# STM32WL_LHCbit.net
KiCad netlist of a schematic drawn in Altium Designer
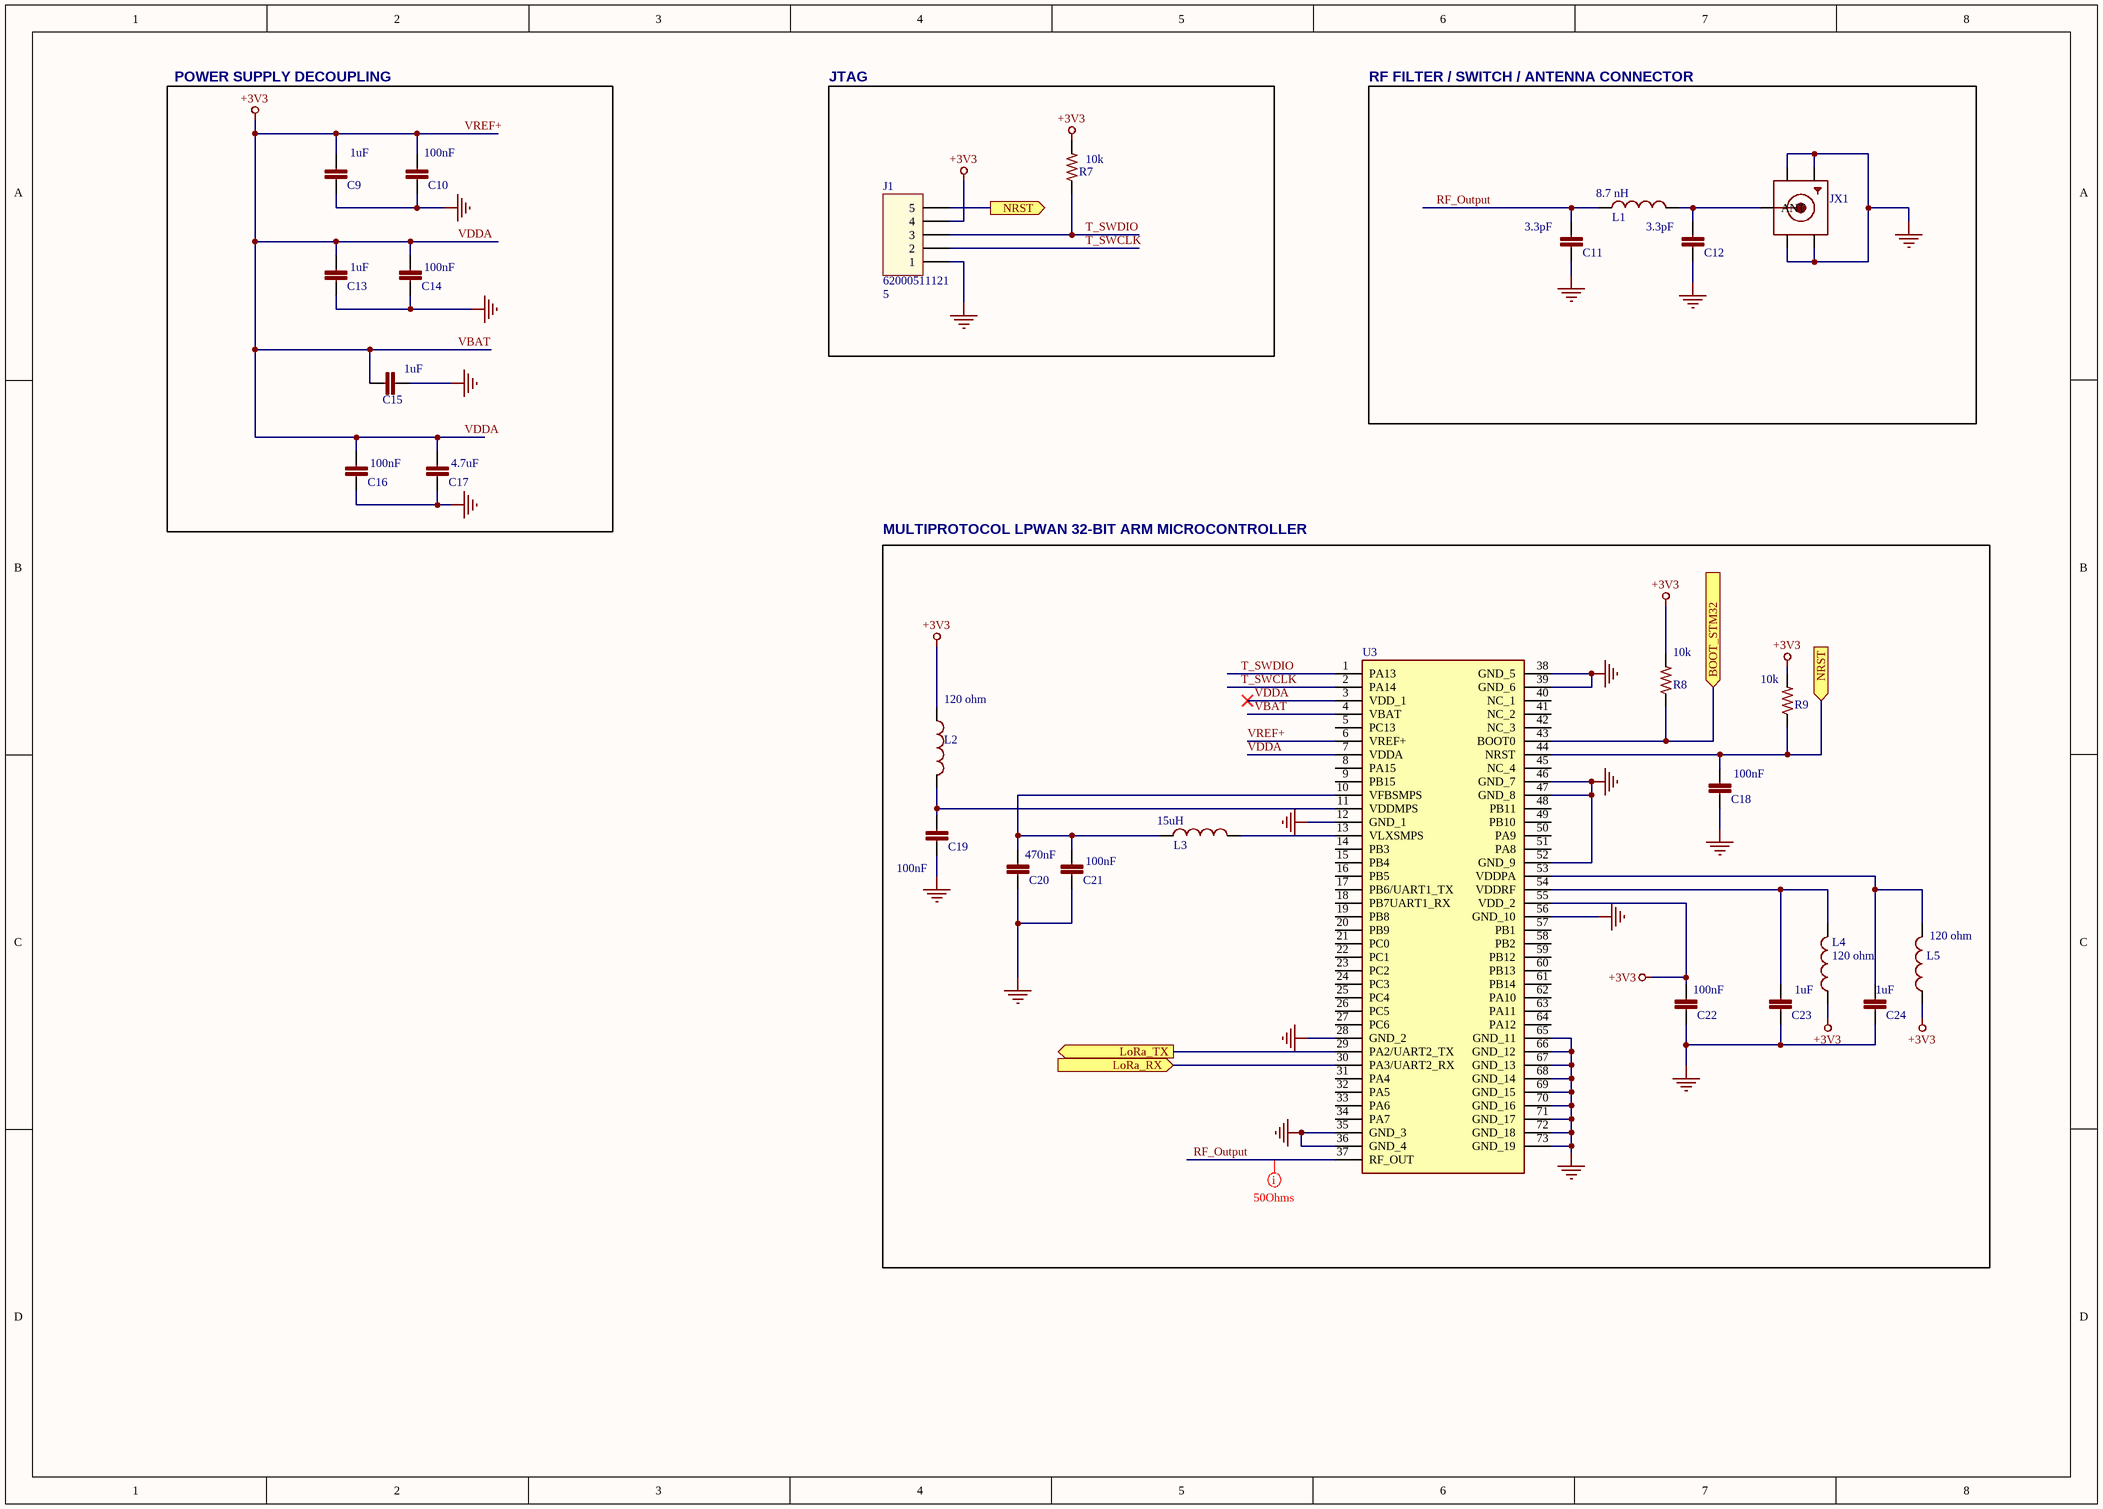
[diagram p0: STM32WL_LHCbit.SchDoc]

(export (version "E")
  (design (tool "Eeschema 10.0.6"))
  (components
    (comp (ref "C9")
      (value "1uF")
      (footprint "C0402")
      (fields (field (name "PART NUMBER") "GRM155C71C105KE11J") (field (name "Comment") "C-EUC0402"))
      (libsource (lib "") (part "C-EUC0402_1"))
    )
    (comp (ref "C10")
      (value "100nF")
      (footprint "C0402")
      (fields (field (name "PART NUMBER") "CGA2B3X7R1E104K050BB") (field (name "Comment") "C-EUC0402"))
      (libsource (lib "") (part "C-EUC0402_1"))
    )
    (comp (ref "C11")
      (value "3.3pF")
      (footprint "C0402")
      (fields (field (name "PART NUMBER") "GRM1555C1H3R3WA01D") (field (name "Comment") "C-EUC0402"))
      (libsource (lib "rcl") (part "C-EUC0402"))
    )
    (comp (ref "C12")
      (value "3.3pF")
      (footprint "C0402")
      (fields (field (name "PART NUMBER") "GRM1555C1H3R3WA01D") (field (name "Comment") "C-EUC0402"))
      (libsource (lib "rcl") (part "C-EUC0402"))
    )
    (comp (ref "C13")
      (value "1uF")
      (footprint "C0402")
      (fields (field (name "PART NUMBER") "GRM155C71C105KE11J") (field (name "Comment") "C-EUC0402"))
      (libsource (lib "") (part "C-EUC0402_1"))
    )
    (comp (ref "C14")
      (value "100nF")
      (footprint "C0402")
      (fields (field (name "PART NUMBER") "CGA2B3X7R1E104K050BB") (field (name "Comment") "C-EUC0402"))
      (libsource (lib "") (part "C-EUC0402_1"))
    )
    (comp (ref "C15")
      (value "1uF")
      (footprint "C0402")
      (fields (field (name "PART NUMBER") "GRM155C71C105KE11J") (field (name "Comment") "C-EUC0402"))
      (libsource (lib "") (part "C-EUC0402_2"))
    )
    (comp (ref "C16")
      (value "100nF")
      (footprint "C0402")
      (fields (field (name "PART NUMBER") "CGA2B3X7R1E104K050BB") (field (name "Comment") "C-EUC0402"))
      (libsource (lib "") (part "C-EUC0402_1"))
    )
    (comp (ref "C17")
      (value "4.7uF")
      (footprint "C0402")
      (fields (field (name "PART NUMBER") "GRM155D80E475ME47J") (field (name "Comment") "C-EUC0402"))
      (libsource (lib "") (part "C-EUC0402_1"))
    )
    (comp (ref "C18")
      (value "100nF")
      (footprint "C0402")
      (fields (field (name "PART NUMBER") "CGA2B3X7R1E104K050BB") (field (name "Comment") "C-EUC0402"))
      (libsource (lib "") (part "C-EUC0402_1"))
    )
    (comp (ref "C19")
      (value "100nF")
      (footprint "C0402")
      (fields (field (name "PART NUMBER") "CGA2B3X7R1E104K050BB") (field (name "Comment") "C-EUC0402"))
      (libsource (lib "") (part "C-EUC0402_1"))
    )
    (comp (ref "C20")
      (value "470nF")
      (footprint "C0402")
      (fields (field (name "PART NUMBER") "0603YD474KAT2A") (field (name "Comment") "C-EUC0402"))
      (libsource (lib "") (part "C-EUC0402_1"))
    )
    (comp (ref "C21")
      (value "100nF")
      (footprint "C0402")
      (fields (field (name "PART NUMBER") "CGA2B3X7R1E104K050BB") (field (name "Comment") "C-EUC0402"))
      (libsource (lib "") (part "C-EUC0402_1"))
    )
    (comp (ref "C22")
      (value "100nF")
      (footprint "C0402")
      (fields (field (name "PART NUMBER") "CGA2B3X7R1E104K050BB") (field (name "Comment") "C-EUC0402"))
      (libsource (lib "") (part "C-EUC0402_1"))
    )
    (comp (ref "C23")
      (value "1uF")
      (footprint "C0402")
      (fields (field (name "PART NUMBER") "GRM155C71C105KE11J") (field (name "Comment") "C-EUC0402"))
      (libsource (lib "") (part "C-EUC0402_1"))
    )
    (comp (ref "C24")
      (value "1uF")
      (footprint "C0402")
      (fields (field (name "PART NUMBER") "GRM155C71C105KE11J") (field (name "Comment") "C-EUC0402"))
      (libsource (lib "") (part "C-EUC0402_1"))
    )
    (comp (ref "J1")
      (value "62000511121")
      (footprint "62000511121")
      (description "WR-PHD 2.00 mm THT Pin Header, 6p")
      (fields (field (name "ALTIUM_VALUE") "5"))
      (libsource (lib "Male_header_200mm") (part "62000511121"))
    )
    (comp (ref "JX1")
      (value "SMACONNECTOR_EDGE_UFL")
      (footprint "SMA_EDGELAUNCH_UFL")
      (fields (field (name "PART NUMBER") "SMA-J-P-H-ST-EM1"))
      (libsource (lib "TE") (part "SMACONNECTOR_EDGE_UFL"))
    )
    (comp (ref "L1")
      (value "8.7 nH")
      (footprint "L0402 - rounded")
      (fields (field (name "PART NUMBER") "LQW15AN8N7G00D") (field (name "Comment") "Ferrite bead 0402"))
      (libsource (lib "rcl") (part "L-US0402"))
    )
    (comp (ref "L2")
      (value "120 ohm")
      (footprint "L0603")
      (fields (field (name "PART NUMBER") "ILHB0603ER121V") (field (name "Comment") "Ferrite bead 0603"))
      (libsource (lib "rcl") (part "L-US0603"))
    )
    (comp (ref "L3")
      (value "15uH")
      (footprint "L0805")
      (fields (field (name "PART NUMBER") "MLZ2012M150WTD25"))
      (libsource (lib "rcl") (part "L-US0805"))
    )
    (comp (ref "L4")
      (value "120 ohm")
      (footprint "L0603")
      (fields (field (name "PART NUMBER") "ILHB0603ER121V") (field (name "Comment") "Ferrite bead 0603"))
      (libsource (lib "rcl") (part "L-US0603"))
    )
    (comp (ref "L5")
      (value "120 ohm")
      (footprint "L0603")
      (fields (field (name "PART NUMBER") "ILHB0603ER121V") (field (name "Comment") "Ferrite bead 0603"))
      (libsource (lib "rcl") (part "L-US0603"))
    )
    (comp (ref "R7")
      (value "10k")
      (footprint "R0402")
      (fields (field (name "PART NUMBER") "CRCW040210K0FKEDC") (field (name "Comment") "R-US_R0402"))
      (libsource (lib "rcl") (part "R-US_R0402"))
    )
    (comp (ref "R8")
      (value "10k")
      (footprint "R0402")
      (fields (field (name "PART NUMBER") "CRCW040210K0FKEDC") (field (name "Comment") "R-US_R0402"))
      (libsource (lib "rcl") (part "R-US_R0402"))
    )
    (comp (ref "R9")
      (value "10k")
      (footprint "R0402")
      (fields (field (name "PART NUMBER") "CRCW040210K0FKEDC") (field (name "Comment") "R-US_R0402"))
      (libsource (lib "rcl") (part "R-US_R0402"))
    )
    (comp (ref "U3")
      (value "RAK3172-SiP")
      (footprint "RAK3172SiP")
      (description "Integrated Circuit")
      (libsource (lib "TE") (part "RAK3172-SiP"))
    )
  )
  (nets
    (net (code "1") (name "+3V3") (class "Default")
      (node (ref "C10") (pin "1") (pinfunction "1_1") (pintype "passive"))
      (node (ref "C13") (pin "1") (pinfunction "1_1") (pintype "passive"))
      (node (ref "C14") (pin "1") (pinfunction "1_1") (pintype "passive"))
      (node (ref "C15") (pin "1") (pinfunction "1_1") (pintype "passive"))
      (node (ref "C16") (pin "1") (pinfunction "1_1") (pintype "passive"))
      (node (ref "C17") (pin "1") (pinfunction "1_1") (pintype "passive"))
      (node (ref "C22") (pin "1") (pinfunction "1_1") (pintype "passive"))
      (node (ref "C9") (pin "1") (pinfunction "1_1") (pintype "passive"))
      (node (ref "J1") (pin "4") (pinfunction "4_4") (pintype "passive"))
      (node (ref "L2") (pin "1") (pinfunction "1_1") (pintype "passive"))
      (node (ref "L4") (pin "1") (pinfunction "1_1") (pintype "passive"))
      (node (ref "L5") (pin "1") (pinfunction "1_1") (pintype "passive"))
      (node (ref "R7") (pin "2") (pinfunction "2_2") (pintype "passive"))
      (node (ref "R8") (pin "2") (pinfunction "2_2") (pintype "passive"))
      (node (ref "R9") (pin "2") (pinfunction "2_2") (pintype "passive"))
      (node (ref "U3") (pin "3") (pinfunction "VDD_1_3") (pintype "passive"))
      (node (ref "U3") (pin "4") (pinfunction "VBAT_4") (pintype "passive"))
      (node (ref "U3") (pin "55") (pinfunction "VDD_2_55") (pintype "passive"))
      (node (ref "U3") (pin "6") (pinfunction "VREF+_6") (pintype "passive"))
      (node (ref "U3") (pin "7") (pinfunction "VDDA_7") (pintype "passive"))
    )
    (net (code "2") (name "/BOOT_STM32") (class "Default")
      (node (ref "R8") (pin "1") (pinfunction "1_1") (pintype "passive"))
      (node (ref "U3") (pin "43") (pinfunction "BOOT0_43") (pintype "passive"))
    )
    (net (code "3") (name "/LoRa_RX") (class "Default")
      (node (ref "U3") (pin "30") (pinfunction "PA3/UART2_RX_30") (pintype "passive"))
    )
    (net (code "4") (name "/LoRa_TX") (class "Default")
      (node (ref "U3") (pin "29") (pinfunction "PA2/UART2_TX_29") (pintype "passive"))
    )
    (net (code "5") (name "/NRST") (class "Default")
      (node (ref "C18") (pin "1") (pinfunction "1_1") (pintype "passive"))
      (node (ref "J1") (pin "5") (pinfunction "5_5") (pintype "passive"))
      (node (ref "R9") (pin "1") (pinfunction "1_1") (pintype "passive"))
      (node (ref "U3") (pin "44") (pinfunction "NRST_44") (pintype "passive"))
    )
    (net (code "6") (name "/RF_Output") (class "Default")
      (node (ref "C11") (pin "2") (pinfunction "2_2") (pintype "passive"))
      (node (ref "L1") (pin "1") (pinfunction "1_1") (pintype "passive"))
      (node (ref "U3") (pin "37") (pinfunction "RF_OUT_37") (pintype "passive"))
    )
    (net (code "7") (name "/T_SWCLK") (class "Default")
      (node (ref "J1") (pin "2") (pinfunction "2_2") (pintype "passive"))
      (node (ref "U3") (pin "2") (pinfunction "PA14_2") (pintype "passive"))
    )
    (net (code "8") (name "/T_SWDIO") (class "Default")
      (node (ref "J1") (pin "3") (pinfunction "3_3") (pintype "passive"))
      (node (ref "R7") (pin "1") (pinfunction "1_1") (pintype "passive"))
      (node (ref "U3") (pin "1") (pinfunction "PA13_1") (pintype "passive"))
    )
    (net (code "9") (name "GND") (class "Default")
      (node (ref "C10") (pin "2") (pinfunction "2_2") (pintype "passive"))
      (node (ref "C11") (pin "1") (pinfunction "1_1") (pintype "passive"))
      (node (ref "C12") (pin "1") (pinfunction "1_1") (pintype "passive"))
      (node (ref "C13") (pin "2") (pinfunction "2_2") (pintype "passive"))
      (node (ref "C14") (pin "2") (pinfunction "2_2") (pintype "passive"))
      (node (ref "C15") (pin "2") (pinfunction "2_2") (pintype "passive"))
      (node (ref "C16") (pin "2") (pinfunction "2_2") (pintype "passive"))
      (node (ref "C17") (pin "2") (pinfunction "2_2") (pintype "passive"))
      (node (ref "C18") (pin "2") (pinfunction "2_2") (pintype "passive"))
      (node (ref "C19") (pin "2") (pinfunction "2_2") (pintype "passive"))
      (node (ref "C20") (pin "2") (pinfunction "2_2") (pintype "passive"))
      (node (ref "C21") (pin "2") (pinfunction "2_2") (pintype "passive"))
      (node (ref "C22") (pin "2") (pinfunction "2_2") (pintype "passive"))
      (node (ref "C23") (pin "2") (pinfunction "2_2") (pintype "passive"))
      (node (ref "C24") (pin "2") (pinfunction "2_2") (pintype "passive"))
      (node (ref "C9") (pin "2") (pinfunction "2_2") (pintype "passive"))
      (node (ref "J1") (pin "1") (pinfunction "1_1") (pintype "passive"))
      (node (ref "JX1") (pin "GND@1") (pinfunction "GND1_GND@1") (pintype "power_in"))
      (node (ref "JX1") (pin "GND@2") (pinfunction "GND2_GND@2") (pintype "power_in"))
      (node (ref "JX1") (pin "GND@3") (pinfunction "GND3_GND@3") (pintype "power_in"))
      (node (ref "JX1") (pin "GND@4") (pinfunction "GND4_GND@4") (pintype "power_in"))
      (node (ref "U3") (pin "12") (pinfunction "GND_1_12") (pintype "passive"))
      (node (ref "U3") (pin "28") (pinfunction "GND_2_28") (pintype "passive"))
      (node (ref "U3") (pin "35") (pinfunction "GND_3_35") (pintype "passive"))
      (node (ref "U3") (pin "36") (pinfunction "GND_4_36") (pintype "passive"))
      (node (ref "U3") (pin "38") (pinfunction "GND_5_38") (pintype "passive"))
      (node (ref "U3") (pin "39") (pinfunction "GND_6_39") (pintype "passive"))
      (node (ref "U3") (pin "46") (pinfunction "GND_7_46") (pintype "passive"))
      (node (ref "U3") (pin "47") (pinfunction "GND_8_47") (pintype "passive"))
      (node (ref "U3") (pin "52") (pinfunction "GND_9_52") (pintype "passive"))
      (node (ref "U3") (pin "56") (pinfunction "GND_10_56") (pintype "passive"))
      (node (ref "U3") (pin "65") (pinfunction "GND_11_65") (pintype "passive"))
      (node (ref "U3") (pin "66") (pinfunction "GND_12_66") (pintype "passive"))
      (node (ref "U3") (pin "67") (pinfunction "GND_13_67") (pintype "passive"))
      (node (ref "U3") (pin "68") (pinfunction "GND_14_68") (pintype "passive"))
      (node (ref "U3") (pin "69") (pinfunction "GND_15_69") (pintype "passive"))
      (node (ref "U3") (pin "70") (pinfunction "GND_16_70") (pintype "passive"))
      (node (ref "U3") (pin "71") (pinfunction "GND_17_71") (pintype "passive"))
      (node (ref "U3") (pin "72") (pinfunction "GND_18_72") (pintype "passive"))
      (node (ref "U3") (pin "73") (pinfunction "GND_19_73") (pintype "passive"))
    )
    (net (code "10") (name "Net-(JX1-ANT)") (class "Default")
      (node (ref "C12") (pin "2") (pinfunction "2_2") (pintype "passive"))
      (node (ref "JX1") (pin "P") (pinfunction "ANT_P") (pintype "passive"))
      (node (ref "L1") (pin "2") (pinfunction "2_2") (pintype "passive"))
    )
    (net (code "11") (name "Net-(U3-VDDMPS)") (class "Default")
      (node (ref "C19") (pin "1") (pinfunction "1_1") (pintype "passive"))
      (node (ref "L2") (pin "2") (pinfunction "2_2") (pintype "passive"))
      (node (ref "U3") (pin "11") (pinfunction "VDDMPS_11") (pintype "passive"))
    )
    (net (code "12") (name "Net-(U3-VDDPA)") (class "Default")
      (node (ref "C24") (pin "1") (pinfunction "1_1") (pintype "passive"))
      (node (ref "L5") (pin "2") (pinfunction "2_2") (pintype "passive"))
      (node (ref "U3") (pin "53") (pinfunction "VDDPA_53") (pintype "passive"))
    )
    (net (code "13") (name "Net-(U3-VDDRF)") (class "Default")
      (node (ref "C23") (pin "1") (pinfunction "1_1") (pintype "passive"))
      (node (ref "L4") (pin "2") (pinfunction "2_2") (pintype "passive"))
      (node (ref "U3") (pin "54") (pinfunction "VDDRF_54") (pintype "passive"))
    )
    (net (code "14") (name "Net-(U3-VFBSMPS)") (class "Default")
      (node (ref "C20") (pin "1") (pinfunction "1_1") (pintype "passive"))
      (node (ref "C21") (pin "1") (pinfunction "1_1") (pintype "passive"))
      (node (ref "L3") (pin "1") (pinfunction "1_1") (pintype "passive"))
      (node (ref "U3") (pin "10") (pinfunction "VFBSMPS_10") (pintype "passive"))
    )
    (net (code "15") (name "Net-(U3-VLXSMPS)") (class "Default")
      (node (ref "L3") (pin "2") (pinfunction "2_2") (pintype "passive"))
      (node (ref "U3") (pin "13") (pinfunction "VLXSMPS_13") (pintype "passive"))
    )
    (net (code "16") (name "unconnected-(U3-NC_1-Pad40)") (class "Default")
      (node (ref "U3") (pin "40") (pinfunction "NC_1_40") (pintype "passive"))
    )
    (net (code "17") (name "unconnected-(U3-NC_2-Pad41)") (class "Default")
      (node (ref "U3") (pin "41") (pinfunction "NC_2_41") (pintype "passive"))
    )
    (net (code "18") (name "unconnected-(U3-NC_3-Pad42)") (class "Default")
      (node (ref "U3") (pin "42") (pinfunction "NC_3_42") (pintype "passive"))
    )
    (net (code "19") (name "unconnected-(U3-NC_4-Pad45)") (class "Default")
      (node (ref "U3") (pin "45") (pinfunction "NC_4_45") (pintype "passive"))
    )
    (net (code "20") (name "unconnected-(U3-PA4-Pad31)") (class "Default")
      (node (ref "U3") (pin "31") (pinfunction "PA4_31") (pintype "passive"))
    )
    (net (code "21") (name "unconnected-(U3-PA5-Pad32)") (class "Default")
      (node (ref "U3") (pin "32") (pinfunction "PA5_32") (pintype "passive"))
    )
    (net (code "22") (name "unconnected-(U3-PA6-Pad33)") (class "Default")
      (node (ref "U3") (pin "33") (pinfunction "PA6_33") (pintype "passive"))
    )
    (net (code "23") (name "unconnected-(U3-PA7-Pad34)") (class "Default")
      (node (ref "U3") (pin "34") (pinfunction "PA7_34") (pintype "passive"))
    )
    (net (code "24") (name "unconnected-(U3-PA8-Pad51)") (class "Default")
      (node (ref "U3") (pin "51") (pinfunction "PA8_51") (pintype "passive"))
    )
    (net (code "25") (name "unconnected-(U3-PA9-Pad50)") (class "Default")
      (node (ref "U3") (pin "50") (pinfunction "PA9_50") (pintype "passive"))
    )
    (net (code "26") (name "unconnected-(U3-PA10-Pad62)") (class "Default")
      (node (ref "U3") (pin "62") (pinfunction "PA10_62") (pintype "passive"))
    )
    (net (code "27") (name "unconnected-(U3-PA11-Pad63)") (class "Default")
      (node (ref "U3") (pin "63") (pinfunction "PA11_63") (pintype "passive"))
    )
    (net (code "28") (name "unconnected-(U3-PA12-Pad64)") (class "Default")
      (node (ref "U3") (pin "64") (pinfunction "PA12_64") (pintype "passive"))
    )
    (net (code "29") (name "unconnected-(U3-PA15-Pad8)") (class "Default")
      (node (ref "U3") (pin "8") (pinfunction "PA15_8") (pintype "passive"))
    )
    (net (code "30") (name "unconnected-(U3-PB1-Pad57)") (class "Default")
      (node (ref "U3") (pin "57") (pinfunction "PB1_57") (pintype "passive"))
    )
    (net (code "31") (name "unconnected-(U3-PB2-Pad58)") (class "Default")
      (node (ref "U3") (pin "58") (pinfunction "PB2_58") (pintype "passive"))
    )
    (net (code "32") (name "unconnected-(U3-PB3-Pad14)") (class "Default")
      (node (ref "U3") (pin "14") (pinfunction "PB3_14") (pintype "passive"))
    )
    (net (code "33") (name "unconnected-(U3-PB4-Pad15)") (class "Default")
      (node (ref "U3") (pin "15") (pinfunction "PB4_15") (pintype "passive"))
    )
    (net (code "34") (name "unconnected-(U3-PB5-Pad16)") (class "Default")
      (node (ref "U3") (pin "16") (pinfunction "PB5_16") (pintype "passive"))
    )
    (net (code "35") (name "unconnected-(U3-PB6{slash}UART1_TX-Pad17)") (class "Default")
      (node (ref "U3") (pin "17") (pinfunction "PB6/UART1_TX_17") (pintype "passive"))
    )
    (net (code "36") (name "unconnected-(U3-PB7UART1_RX-Pad18)") (class "Default")
      (node (ref "U3") (pin "18") (pinfunction "PB7UART1_RX_18") (pintype "passive"))
    )
    (net (code "37") (name "unconnected-(U3-PB8-Pad19)") (class "Default")
      (node (ref "U3") (pin "19") (pinfunction "PB8_19") (pintype "passive"))
    )
    (net (code "38") (name "unconnected-(U3-PB9-Pad20)") (class "Default")
      (node (ref "U3") (pin "20") (pinfunction "PB9_20") (pintype "passive"))
    )
    (net (code "39") (name "unconnected-(U3-PB10-Pad49)") (class "Default")
      (node (ref "U3") (pin "49") (pinfunction "PB10_49") (pintype "passive"))
    )
    (net (code "40") (name "unconnected-(U3-PB11-Pad48)") (class "Default")
      (node (ref "U3") (pin "48") (pinfunction "PB11_48") (pintype "passive"))
    )
    (net (code "41") (name "unconnected-(U3-PB12-Pad59)") (class "Default")
      (node (ref "U3") (pin "59") (pinfunction "PB12_59") (pintype "passive"))
    )
    (net (code "42") (name "unconnected-(U3-PB13-Pad60)") (class "Default")
      (node (ref "U3") (pin "60") (pinfunction "PB13_60") (pintype "passive"))
    )
    (net (code "43") (name "unconnected-(U3-PB14-Pad61)") (class "Default")
      (node (ref "U3") (pin "61") (pinfunction "PB14_61") (pintype "passive"))
    )
    (net (code "44") (name "unconnected-(U3-PB15-Pad9)") (class "Default")
      (node (ref "U3") (pin "9") (pinfunction "PB15_9") (pintype "passive"))
    )
    (net (code "45") (name "unconnected-(U3-PC0-Pad21)") (class "Default")
      (node (ref "U3") (pin "21") (pinfunction "PC0_21") (pintype "passive"))
    )
    (net (code "46") (name "unconnected-(U3-PC1-Pad22)") (class "Default")
      (node (ref "U3") (pin "22") (pinfunction "PC1_22") (pintype "passive"))
    )
    (net (code "47") (name "unconnected-(U3-PC2-Pad23)") (class "Default")
      (node (ref "U3") (pin "23") (pinfunction "PC2_23") (pintype "passive"))
    )
    (net (code "48") (name "unconnected-(U3-PC3-Pad24)") (class "Default")
      (node (ref "U3") (pin "24") (pinfunction "PC3_24") (pintype "passive"))
    )
    (net (code "49") (name "unconnected-(U3-PC4-Pad25)") (class "Default")
      (node (ref "U3") (pin "25") (pinfunction "PC4_25") (pintype "passive"))
    )
    (net (code "50") (name "unconnected-(U3-PC5-Pad26)") (class "Default")
      (node (ref "U3") (pin "26") (pinfunction "PC5_26") (pintype "passive"))
    )
    (net (code "51") (name "unconnected-(U3-PC6-Pad27)") (class "Default")
      (node (ref "U3") (pin "27") (pinfunction "PC6_27") (pintype "passive"))
    )
    (net (code "52") (name "unconnected-(U3-PC13-Pad5)") (class "Default")
      (node (ref "U3") (pin "5") (pinfunction "PC13_5") (pintype "passive"))
    )
  )
)
